# 01_Power.net
KiCad netlist of a schematic drawn in Altium Designer
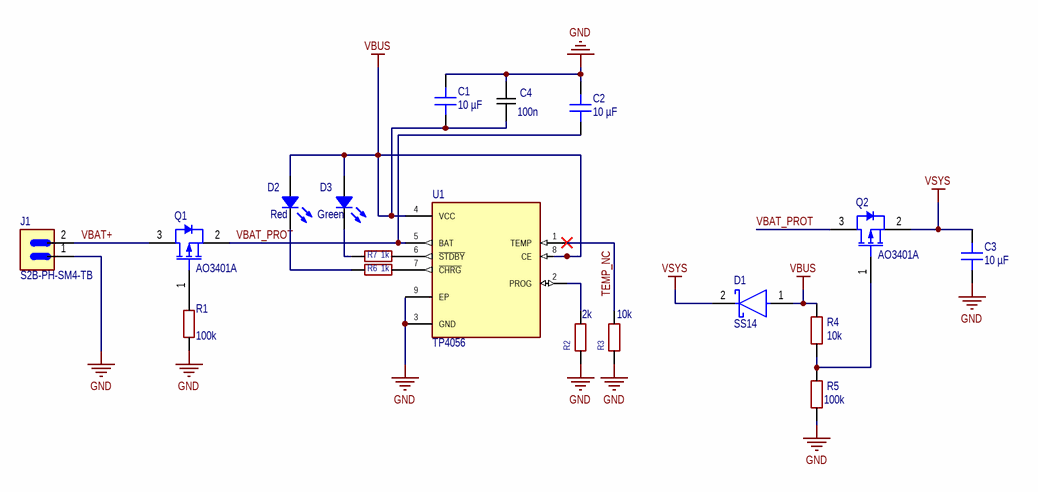
[diagram p0: 01_Power.SchDoc]

(export (version "E")
  (design (tool "Eeschema 10.0.6"))
  (components
    (comp (ref "C1")
      (value "10 µF")
      (footprint "CAP 0603_1608")
      (description "CAP CER 10UF 10V X6S 0603")
      (fields
        (field (name "PART NUMBER") "GRM188C81A106MA73D")
        (field (name "CAPACITANCE") "10 µF")
        (field (name "MANUFACTURER") "Murata Electronics")
      )
      (libsource (lib "Celestial Altium Library - altium_library") (part "Capacitor"))
    )
    (comp (ref "C2")
      (value "10 µF")
      (footprint "CAP 0603_1608")
      (description "CAP CER 10UF 10V X6S 0603")
      (fields
        (field (name "PART NUMBER") "GRM188C81A106MA73D")
        (field (name "CAPACITANCE") "10 µF")
        (field (name "MANUFACTURER") "Murata Electronics")
      )
      (libsource (lib "Celestial Altium Library - altium_library") (part "Capacitor"))
    )
    (comp (ref "C3")
      (value "10 µF")
      (footprint "CAP 0603_1608")
      (description "CAP CER 10UF 10V X6S 0603")
      (fields
        (field (name "PART NUMBER") "GRM188C81A106MA73D")
        (field (name "CAPACITANCE") "10 µF")
        (field (name "MANUFACTURER") "Murata Electronics")
      )
      (libsource (lib "Celestial Altium Library - altium_library") (part "Capacitor"))
    )
    (comp (ref "C4")
      (value "100n")
      (footprint "CAPC1608(0603)N")
      (description "0,1uF 0603 50V X7R  +/-20%")
      (fields
        (field (name "PART NUMBER") "UMF107B7104MAHT")
        (field (name "MOUSER PART NUMBER") "963-UMF107B7104MAHT")
      )
      (libsource (lib "SssAccesDatbase") (part "Cap"))
    )
    (comp (ref "D1")
      (value "SS14")
      (footprint "FP-403AE-MFG")
      (description "DIODE SCHOTTKY 40V 1A SMA")
      (fields
        (field (name "MANUFACTURER") "ON Semiconductor")
        (field (name "OCTOPART") "https://octopart.com/ss14-on+semiconductor-29205033")
      )
      (libsource (lib "Altium Content Vault") (part "360ad2f4ac25a952324d13796385471"))
    )
    (comp (ref "D2")
      (value "Red")
      (footprint "LED 0603_1608 RED")
      (description "LED RED CLEAR 0603 SMD")
      (fields (field (name "PART NUMBER") "QBLP601-R") (field (name "MANUFACTURER") "QT Brightek (QTB)"))
      (libsource (lib "Celestial Altium Library - altium_library") (part "LED"))
    )
    (comp (ref "D3")
      (value "Green")
      (footprint "LED 0603_1608 GREEN")
      (description "LED GREEN CLEAR 0603 SMD")
      (fields
        (field (name "PART NUMBER") "QTLP601C4TR")
        (field (name "MANUFACTURER") "Everlight Electronics Co Ltd")
      )
      (libsource (lib "Celestial Altium Library - altium_library") (part "LED"))
    )
    (comp (ref "J1")
      (value "S2B-PH-SM4-TB")
      (footprint "JST_S2B-PH-SM4-TB")
      (description "Connector Header Surface Mount, Right Angle 2 position 0.079 (2.00mm)")
      (fields (field (name "MF") "JST Sales"))
      (libsource (lib "PicoLimitSwitchShield") (part "S2B-PH-SM4-TB"))
    )
    (comp (ref "Q1")
      (value "AO3401A")
      (footprint "AO-SOT-23-3L_V")
      (description "P-Channel MOSFET, 30 V, 4 A, -55 to 150 degC, 3-Pin SOT-23-3L, RoHS, Tape and Reel")
      (fields (field (name "MANUFACTURER") "Alpha and Omega"))
      (libsource (lib "Altium Content Vault") (part "PEMOS-GSD-3"))
    )
    (comp (ref "Q2")
      (value "AO3401A")
      (footprint "AO-SOT-23-3L_V")
      (description "P-Channel MOSFET, 30 V, 4 A, -55 to 150 degC, 3-Pin SOT-23-3L, RoHS, Tape and Reel")
      (fields (field (name "MANUFACTURER") "Alpha and Omega"))
      (libsource (lib "Altium Content Vault") (part "PEMOS-GSD-3"))
    )
    (comp (ref "R1")
      (value "100k")
      (footprint "RESC1608(0603)N")
      (description "RES SMD 0603 100k 1% 100ppm")
      (fields
        (field (name "PART NUMBER") "CRCW0603100KFKEAC")
        (field (name "MOUSER PART NUMBER") "71-CRCW0603100KFKEAC")
      )
      (libsource (lib "SssAccesDatbase") (part "Resistor general"))
    )
    (comp (ref "R2")
      (value "2k")
      (footprint "REZKemet 0402")
      (description "RES SMD 0402 2k 5% 100ppm")
      (fields
        (field (name "PART NUMBER") "RC0402JR-072KL")
        (field (name "DIGI-KEY PART NUMBER") "311-2.0KJRCT-ND")
      )
      (libsource (lib "SssAccesDatbase") (part "Resistor general"))
    )
    (comp (ref "R3")
      (value "10k")
      (footprint "RESC1608(0603)N")
      (description "RES SMD 0603 10k 1% 100ppm")
      (fields
        (field (name "PART NUMBER") "RC0603FR-0710KL")
        (field (name "MOUSER PART NUMBER") "603-RC0603FR-0710KL")
      )
      (libsource (lib "SssAccesDatbase") (part "Resistor general"))
    )
    (comp (ref "R4")
      (value "10k")
      (footprint "RESC1608(0603)N")
      (description "RES SMD 0603 10k 1% 100ppm")
      (fields
        (field (name "PART NUMBER") "RC0603FR-0710KL")
        (field (name "MOUSER PART NUMBER") "603-RC0603FR-0710KL")
      )
      (libsource (lib "SssAccesDatbase") (part "Resistor general"))
    )
    (comp (ref "R5")
      (value "100k")
      (footprint "RESC1608(0603)N")
      (description "RES SMD 0603 100k 0.5% 50ppm")
      (fields
        (field (name "PART NUMBER") "RT0603DRE07100KL")
        (field (name "MOUSER PART NUMBER") "603-RT0603DRE07100KL")
      )
      (libsource (lib "SssAccesDatbase") (part "Resistor general"))
    )
    (comp (ref "R6")
      (value "1k")
      (footprint "RESC1608(0603)N")
      (description "RES SMD 0603 1.00k 0.5% 50ppm")
      (fields
        (field (name "PART NUMBER") "RT0603DRE071KL")
        (field (name "MOUSER PART NUMBER") "603-RT0603DRE071KL")
      )
      (libsource (lib "") (part "Resistor general_1"))
    )
    (comp (ref "R7")
      (value "1k")
      (footprint "RESC1608(0603)N")
      (description "RES SMD 0603 1.00k 0.5% 50ppm")
      (fields
        (field (name "PART NUMBER") "RT0603DRE071KL")
        (field (name "MOUSER PART NUMBER") "603-RT0603DRE071KL")
      )
      (libsource (lib "") (part "Resistor general_1"))
    )
    (comp (ref "U1")
      (value "TP4056")
      (footprint "SOP127P600X175-9N")
      (description "Complete single cell Li-Ion battery with a constant current / constant voltage linear charger")
      (fields (field (name "MF") "NanJing Top Power ASIC Corp."))
      (libsource (lib "PicoLimitSwitchShield") (part "TP4056"))
    )
  )
  (nets
    (net (code "1") (name "/TEMP_NC") (class "Default")
      (node (ref "R3") (pin "2") (pinfunction "2_2") (pintype "passive"))
      (node (ref "U1") (pin "1") (pinfunction "TEMP_1") (pintype "input"))
    )
    (net (code "2") (name "/VBAT+") (class "Default")
      (node (ref "J1") (pin "2") (pinfunction "2_2") (pintype "passive"))
      (node (ref "Q1") (pin "3") (pinfunction "DRAIN_3") (pintype "passive"))
    )
    (net (code "3") (name "/VBAT_PROT") (class "Default")
      (node (ref "C2") (pin "2") (pinfunction "2_2") (pintype "passive"))
      (node (ref "Q1") (pin "2") (pinfunction "SOURCE_2") (pintype "passive"))
      (node (ref "Q2") (pin "3") (pinfunction "DRAIN_3") (pintype "passive"))
      (node (ref "U1") (pin "5") (pinfunction "BAT_5") (pintype "output"))
    )
    (net (code "4") (name "GND") (class "Default")
      (node (ref "C1") (pin "1") (pinfunction "1_1") (pintype "passive"))
      (node (ref "C2") (pin "1") (pinfunction "1_1") (pintype "passive"))
      (node (ref "C3") (pin "2") (pinfunction "2_2") (pintype "passive"))
      (node (ref "C4") (pin "2") (pinfunction "2_2") (pintype "passive"))
      (node (ref "J1") (pin "1") (pinfunction "1_1") (pintype "passive"))
      (node (ref "R1") (pin "1") (pinfunction "1_1") (pintype "passive"))
      (node (ref "R2") (pin "1") (pinfunction "1_1") (pintype "passive"))
      (node (ref "R3") (pin "1") (pinfunction "1_1") (pintype "passive"))
      (node (ref "R5") (pin "1") (pinfunction "1_1") (pintype "passive"))
      (node (ref "U1") (pin "3") (pinfunction "GND_3") (pintype "power_in"))
    )
    (net (code "5") (name "Net-(D2-Pad2)") (class "Default")
      (node (ref "D2") (pin "2") (pinfunction "2_2") (pintype "passive"))
      (node (ref "R6") (pin "1") (pinfunction "1_1") (pintype "passive"))
    )
    (net (code "6") (name "Net-(D3-Pad2)") (class "Default")
      (node (ref "D3") (pin "2") (pinfunction "2_2") (pintype "passive"))
      (node (ref "R7") (pin "1") (pinfunction "1_1") (pintype "passive"))
    )
    (net (code "7") (name "Net-(Q1-GATE)") (class "Default")
      (node (ref "Q1") (pin "1") (pinfunction "GATE_1") (pintype "passive"))
      (node (ref "R1") (pin "2") (pinfunction "2_2") (pintype "passive"))
    )
    (net (code "8") (name "Net-(Q2-GATE)") (class "Default")
      (node (ref "Q2") (pin "1") (pinfunction "GATE_1") (pintype "passive"))
      (node (ref "R4") (pin "1") (pinfunction "1_1") (pintype "passive"))
      (node (ref "R5") (pin "2") (pinfunction "2_2") (pintype "passive"))
    )
    (net (code "9") (name "Net-(U1-PROG)") (class "Default")
      (node (ref "R2") (pin "2") (pinfunction "2_2") (pintype "passive"))
      (node (ref "U1") (pin "2") (pinfunction "PROG_2") (pintype "bidirectional"))
    )
    (net (code "10") (name "Net-(U1-~{CHRG})") (class "Default")
      (node (ref "R6") (pin "2") (pinfunction "2_2") (pintype "passive"))
      (node (ref "U1") (pin "7") (pinfunction "~{CHRG}_7") (pintype "output"))
    )
    (net (code "11") (name "Net-(U1-~{STDBY})") (class "Default")
      (node (ref "R7") (pin "2") (pinfunction "2_2") (pintype "passive"))
      (node (ref "U1") (pin "6") (pinfunction "~{STDBY}_6") (pintype "output"))
    )
    (net (code "12") (name "VBUS") (class "Default")
      (node (ref "C1") (pin "2") (pinfunction "2_2") (pintype "passive"))
      (node (ref "C4") (pin "1") (pinfunction "1_1") (pintype "passive"))
      (node (ref "D1") (pin "1") (pinfunction "A_1") (pintype "passive"))
      (node (ref "D2") (pin "1") (pinfunction "1_1") (pintype "passive"))
      (node (ref "D3") (pin "1") (pinfunction "1_1") (pintype "passive"))
      (node (ref "R4") (pin "2") (pinfunction "2_2") (pintype "passive"))
      (node (ref "U1") (pin "4") (pinfunction "VCC_4") (pintype "power_in"))
      (node (ref "U1") (pin "8") (pinfunction "CE_8") (pintype "input"))
    )
    (net (code "13") (name "VSYS") (class "Default")
      (node (ref "C3") (pin "1") (pinfunction "1_1") (pintype "passive"))
      (node (ref "D1") (pin "2") (pinfunction "C_2") (pintype "passive"))
      (node (ref "Q2") (pin "2") (pinfunction "SOURCE_2") (pintype "passive"))
    )
    (net (code "14") (name "unconnected-(U1-EP-Pad9)") (class "Default")
      (node (ref "U1") (pin "9") (pinfunction "EP_9") (pintype "passive"))
    )
  )
)
